# SaLFrostburn.net
KiCad netlist of a schematic drawn in EAGLE
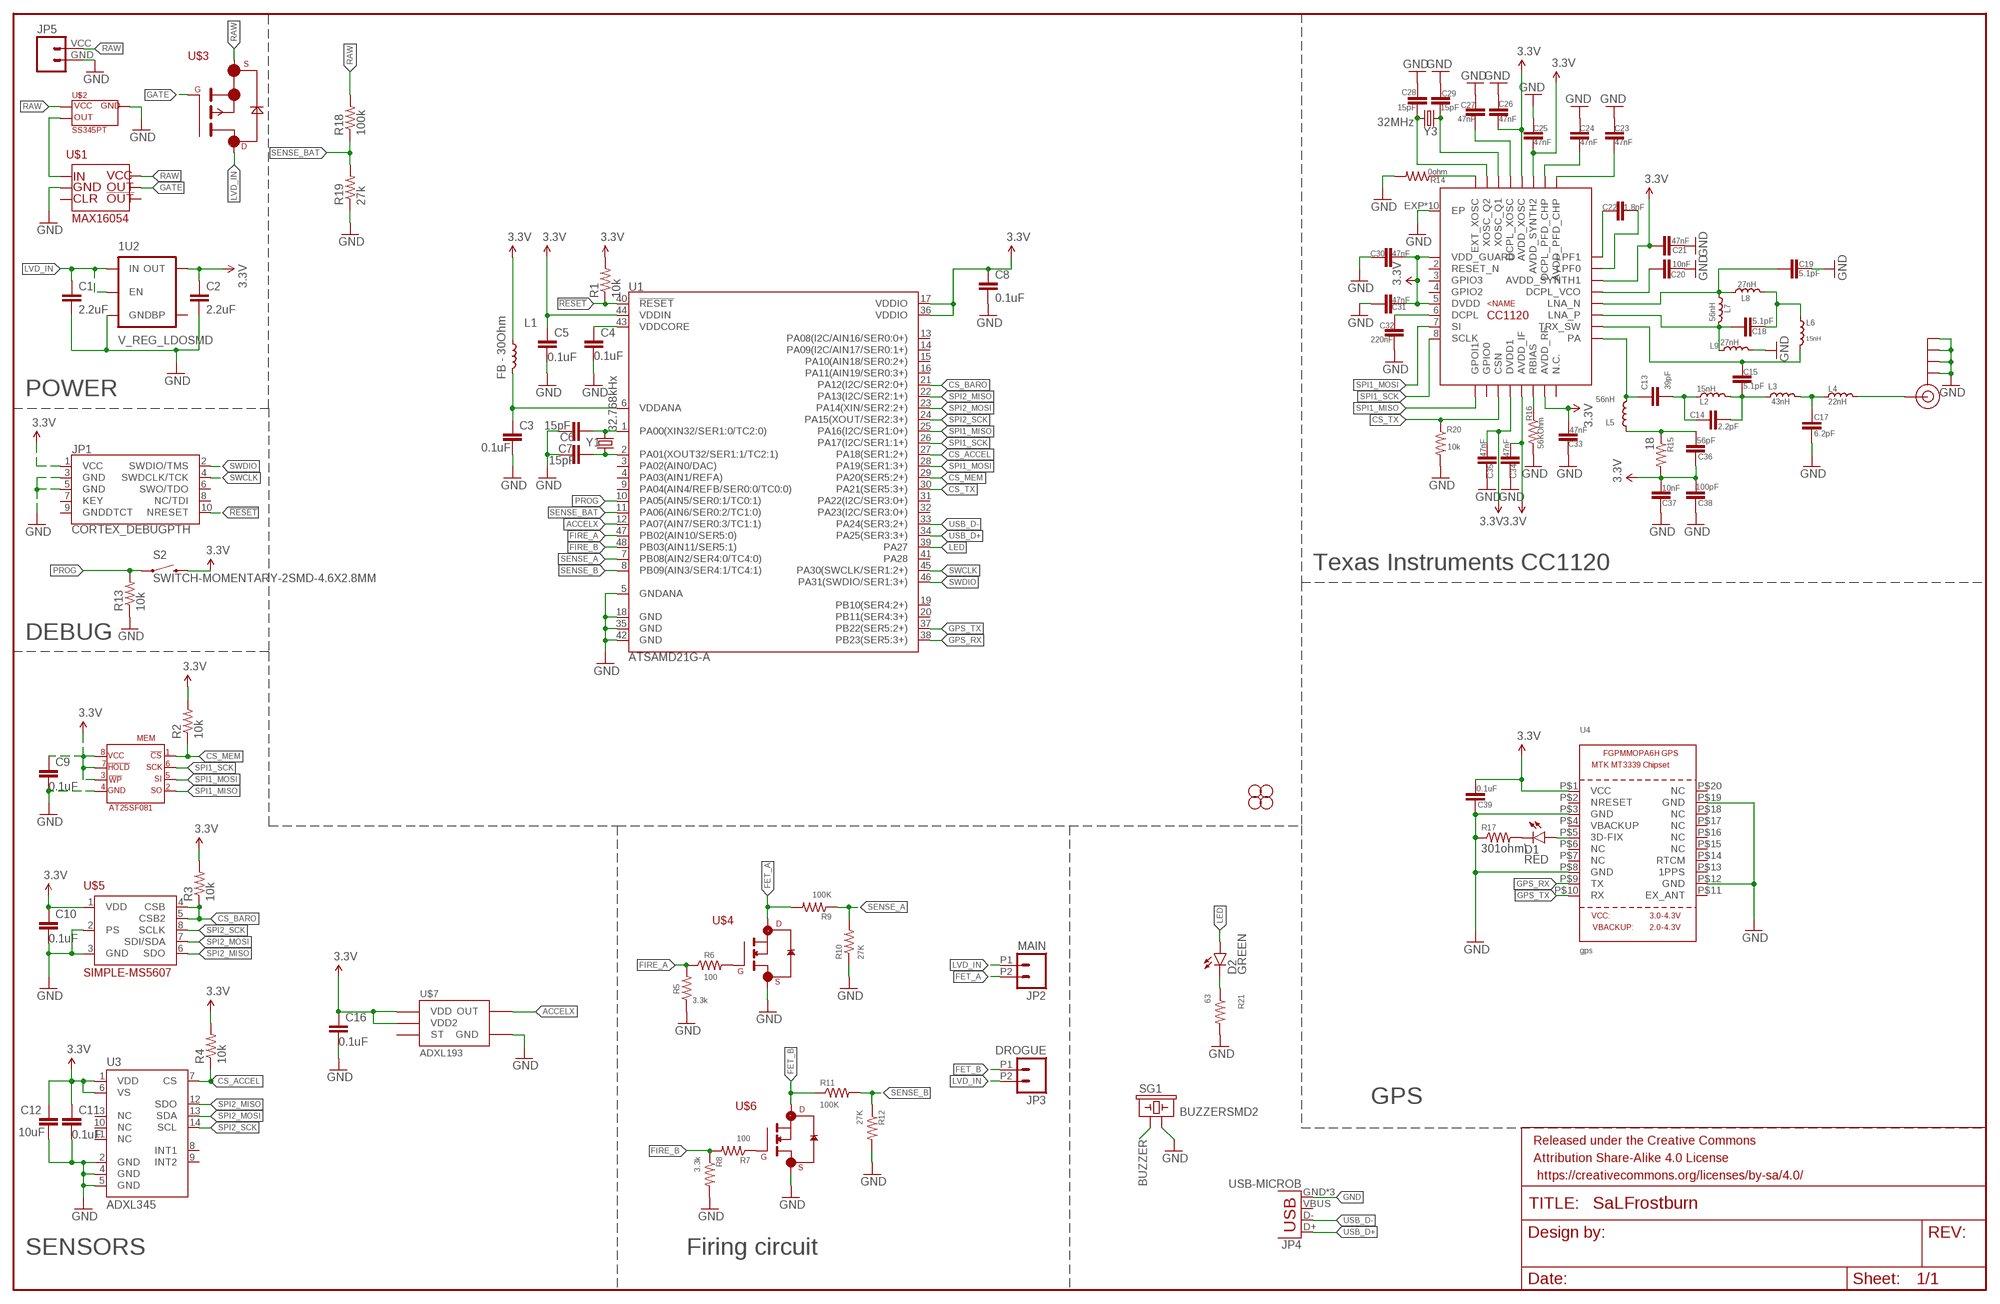
[diagram p0: schematic, sheet 1]

(export (version "E")
  (design (tool "Eeschema 10.0.6"))
  (components
    (comp (ref "1U2")
      (value "V_REG_LDOSMD")
      (footprint "eagle-import:SOT23-5")
      (libsource (lib "eagle-import") (part "V_REG_LDOSMD"))
    )
    (comp (ref "C1")
      (value "2.2uF")
      (footprint "eagle-import:0603-CAP")
      (libsource (lib "eagle-import") (part "CAP0603-CAP"))
    )
    (comp (ref "C2")
      (value "2.2uF")
      (footprint "eagle-import:0603-CAP")
      (libsource (lib "eagle-import") (part "CAP0603-CAP"))
    )
    (comp (ref "C3")
      (value "0.1uF")
      (footprint "eagle-import:0402-CAP")
      (libsource (lib "eagle-import") (part "SparkFun-Passives_CAP0402-CAP"))
    )
    (comp (ref "C4")
      (value "0.1uF")
      (footprint "eagle-import:0402-CAP")
      (libsource (lib "eagle-import") (part "SparkFun-Passives_CAP0402-CAP"))
    )
    (comp (ref "C5")
      (value "0.1uF")
      (footprint "eagle-import:0402-CAP")
      (libsource (lib "eagle-import") (part "SparkFun-Passives_CAP0402-CAP"))
    )
    (comp (ref "C6")
      (value "15pF")
      (footprint "eagle-import:0402-CAP")
      (libsource (lib "eagle-import") (part "SparkFun-Passives_CAP0402-CAP"))
    )
    (comp (ref "C7")
      (value "15pF")
      (footprint "eagle-import:0402-CAP")
      (libsource (lib "eagle-import") (part "SparkFun-Passives_CAP0402-CAP"))
    )
    (comp (ref "C8")
      (value "0.1uF")
      (footprint "eagle-import:0402-CAP")
      (libsource (lib "eagle-import") (part "SparkFun-Passives_CAP0402-CAP"))
    )
    (comp (ref "C9")
      (value "0.1uF")
      (footprint "eagle-import:0402-CAP")
      (libsource (lib "eagle-import") (part "SparkFun-Passives_CAP0402-CAP"))
    )
    (comp (ref "C10")
      (value "0.1uF")
      (footprint "eagle-import:0402-CAP")
      (libsource (lib "eagle-import") (part "SparkFun-Passives_CAP0402-CAP"))
    )
    (comp (ref "C11")
      (value "0.1uF")
      (footprint "eagle-import:0402-CAP")
      (libsource (lib "eagle-import") (part "SparkFun-Passives_CAP0402-CAP"))
    )
    (comp (ref "C12")
      (value "10uF")
      (footprint "eagle-import:0402-CAP")
      (libsource (lib "eagle-import") (part "SparkFun-Passives_CAP0402-CAP"))
    )
    (comp (ref "C13")
      (value "39pF")
      (footprint "eagle-import:0402-CAP")
      (libsource (lib "eagle-import") (part "CAP0402-CAP"))
    )
    (comp (ref "C14")
      (value "2.2pF")
      (footprint "eagle-import:0402-CAP")
      (libsource (lib "eagle-import") (part "CAP0402-CAP"))
    )
    (comp (ref "C15")
      (value "5.1pF")
      (footprint "eagle-import:0402-CAP")
      (libsource (lib "eagle-import") (part "CAP0402-CAP"))
    )
    (comp (ref "C16")
      (value "0.1uF")
      (footprint "eagle-import:0402-CAP")
      (libsource (lib "eagle-import") (part "SparkFun-Passives_CAP0402-CAP"))
    )
    (comp (ref "C17")
      (value "6.2pF")
      (footprint "eagle-import:0402-CAP")
      (libsource (lib "eagle-import") (part "CAP0402-CAP"))
    )
    (comp (ref "C18")
      (value "5.1pF")
      (footprint "eagle-import:0402-CAP")
      (libsource (lib "eagle-import") (part "CAP0402-CAP"))
    )
    (comp (ref "C19")
      (value "5.1pF")
      (footprint "eagle-import:0402-CAP")
      (libsource (lib "eagle-import") (part "CAP0402-CAP"))
    )
    (comp (ref "C20")
      (value "10nF")
      (footprint "eagle-import:0402-CAP")
      (libsource (lib "eagle-import") (part "CAP0402-CAP"))
    )
    (comp (ref "C21")
      (value "47nF")
      (footprint "eagle-import:0402-CAP")
      (libsource (lib "eagle-import") (part "CAP0402-CAP"))
    )
    (comp (ref "C22")
      (value "1.8nF")
      (footprint "eagle-import:0402-CAP")
      (libsource (lib "eagle-import") (part "CAP0402-CAP"))
    )
    (comp (ref "C23")
      (value "47nF")
      (footprint "eagle-import:0402-CAP")
      (libsource (lib "eagle-import") (part "CAP0402-CAP"))
    )
    (comp (ref "C24")
      (value "47nF")
      (footprint "eagle-import:0402-CAP")
      (libsource (lib "eagle-import") (part "CAP0402-CAP"))
    )
    (comp (ref "C25")
      (value "47nF")
      (footprint "eagle-import:0402-CAP")
      (libsource (lib "eagle-import") (part "CAP0402-CAP"))
    )
    (comp (ref "C26")
      (value "47nF")
      (footprint "eagle-import:0402-CAP")
      (libsource (lib "eagle-import") (part "CAP0402-CAP"))
    )
    (comp (ref "C27")
      (value "47nF")
      (footprint "eagle-import:0402-CAP")
      (libsource (lib "eagle-import") (part "CAP0402-CAP"))
    )
    (comp (ref "C28")
      (value "15pF")
      (footprint "eagle-import:0402-CAP")
      (libsource (lib "eagle-import") (part "CAP0402-CAP"))
    )
    (comp (ref "C29")
      (value "15pF")
      (footprint "eagle-import:0402-CAP")
      (libsource (lib "eagle-import") (part "CAP0402-CAP"))
    )
    (comp (ref "C30")
      (value "47nF")
      (footprint "eagle-import:0402-CAP")
      (libsource (lib "eagle-import") (part "CAP0402-CAP"))
    )
    (comp (ref "C31")
      (value "47nF")
      (footprint "eagle-import:0402-CAP")
      (libsource (lib "eagle-import") (part "CAP0402-CAP"))
    )
    (comp (ref "C32")
      (value "220nF")
      (footprint "eagle-import:0402-CAP")
      (libsource (lib "eagle-import") (part "CAP0402-CAP"))
    )
    (comp (ref "C33")
      (value "47nF")
      (footprint "eagle-import:0402-CAP")
      (libsource (lib "eagle-import") (part "CAP0402-CAP"))
    )
    (comp (ref "C34")
      (value "47nF")
      (footprint "eagle-import:0402-CAP")
      (libsource (lib "eagle-import") (part "CAP0402-CAP"))
    )
    (comp (ref "C35")
      (value "47nF")
      (footprint "eagle-import:0402-CAP")
      (libsource (lib "eagle-import") (part "CAP0402-CAP"))
    )
    (comp (ref "C36")
      (value "56pF")
      (footprint "eagle-import:0402-CAP")
      (libsource (lib "eagle-import") (part "CAP0402-CAP"))
    )
    (comp (ref "C37")
      (value "10nF")
      (footprint "eagle-import:0402-CAP")
      (libsource (lib "eagle-import") (part "CAP0402-CAP"))
    )
    (comp (ref "C38")
      (value "100pF")
      (footprint "eagle-import:0402-CAP")
      (libsource (lib "eagle-import") (part "CAP0402-CAP"))
    )
    (comp (ref "C39")
      (value "0.1uF")
      (footprint "eagle-import:0402-CAP")
      (libsource (lib "eagle-import") (part "CAP0402-CAP"))
    )
    (comp (ref "D1")
      (value "RED")
      (footprint "eagle-import:LED-0603")
      (libsource (lib "eagle-import") (part "LED-RED0603"))
    )
    (comp (ref "D2")
      (value "GREEN")
      (footprint "eagle-import:LED-1206")
      (libsource (lib "eagle-import") (part "LED-GREEN1206"))
    )
    (comp (ref "FRAME1")
      (value "FRAME-LEDGER")
      (footprint "eagle-import:CREATIVE_COMMONS")
      (libsource (lib "eagle-import") (part "FRAME-LEDGER"))
    )
    (comp (ref "J$1")
      (value "SMA_EDGE")
      (footprint "eagle-import:SMA-EDGE")
      (libsource (lib "eagle-import") (part "SMA_EDGE"))
    )
    (comp (ref "JP1")
      (value "CORTEX_DEBUGPTH")
      (footprint "eagle-import:2X5-PTH-1.27MM")
      (libsource (lib "eagle-import") (part "CORTEX_DEBUGPTH"))
    )
    (comp (ref "JP2")
      (value "MAIN")
      (footprint "eagle-import:1X02_2.54_SCREWTERM")
      (libsource (lib "eagle-import") (part "M022.54MM_SCREWTERM"))
    )
    (comp (ref "JP3")
      (value "DROGUE")
      (footprint "eagle-import:1X02_2.54_SCREWTERM")
      (libsource (lib "eagle-import") (part "M022.54MM_SCREWTERM"))
    )
    (comp (ref "JP4")
      (value "USB-MICROB")
      (footprint "eagle-import:USB-MICROB")
      (libsource (lib "eagle-import") (part "USB-MICROB"))
    )
    (comp (ref "JP5")
      (value "M024UCON-15767")
      (footprint "eagle-import:JST-2-SMD-VERT")
      (libsource (lib "eagle-import") (part "M024UCON-15767"))
    )
    (comp (ref "L1")
      (value "FB - 30Ohm")
      (footprint "eagle-import:0603")
      (libsource (lib "eagle-import") (part "INDUCTOR0603"))
    )
    (comp (ref "L2")
      (value "15nH")
      (footprint "eagle-import:C0402")
      (libsource (lib "eagle-import") (part "INDUCTOR0402"))
    )
    (comp (ref "L3")
      (value "43nH")
      (footprint "eagle-import:C0402")
      (libsource (lib "eagle-import") (part "INDUCTOR0402"))
    )
    (comp (ref "L4")
      (value "22nH")
      (footprint "eagle-import:C0402")
      (libsource (lib "eagle-import") (part "INDUCTOR0402"))
    )
    (comp (ref "L5")
      (value "56nH")
      (footprint "eagle-import:C0402")
      (libsource (lib "eagle-import") (part "INDUCTOR0402"))
    )
    (comp (ref "L6")
      (value "15nH")
      (footprint "eagle-import:C0402")
      (libsource (lib "eagle-import") (part "INDUCTOR0402"))
    )
    (comp (ref "L7")
      (value "56nH")
      (footprint "eagle-import:C0402")
      (libsource (lib "eagle-import") (part "INDUCTOR0402"))
    )
    (comp (ref "L8")
      (value "27nH")
      (footprint "eagle-import:C0402")
      (libsource (lib "eagle-import") (part "INDUCTOR0402"))
    )
    (comp (ref "L9")
      (value "27nH")
      (footprint "eagle-import:C0402")
      (libsource (lib "eagle-import") (part "INDUCTOR0402"))
    )
    (comp (ref "MEM")
      (value "AT25SF081")
      (footprint "eagle-import:AT25SF081")
      (libsource (lib "eagle-import") (part "AT25SF081"))
    )
    (comp (ref "R1")
      (value "10k")
      (footprint "eagle-import:0402-RES")
      (libsource (lib "eagle-import") (part "RESISTOR0402-RES"))
    )
    (comp (ref "R2")
      (value "10k")
      (footprint "eagle-import:0402-RES")
      (libsource (lib "eagle-import") (part "RESISTOR0402-RES"))
    )
    (comp (ref "R3")
      (value "10k")
      (footprint "eagle-import:0402-RES")
      (libsource (lib "eagle-import") (part "RESISTOR0402-RES"))
    )
    (comp (ref "R4")
      (value "10k")
      (footprint "eagle-import:0402-RES")
      (libsource (lib "eagle-import") (part "RESISTOR0402-RES"))
    )
    (comp (ref "R5")
      (value "3.3k")
      (footprint "eagle-import:0402-RES")
      (libsource (lib "eagle-import") (part "RESISTOR0402"))
    )
    (comp (ref "R6")
      (value "100")
      (footprint "eagle-import:0402-RES")
      (libsource (lib "eagle-import") (part "RESISTOR0402"))
    )
    (comp (ref "R7")
      (value "100")
      (footprint "eagle-import:0402-RES")
      (libsource (lib "eagle-import") (part "RESISTOR0402"))
    )
    (comp (ref "R8")
      (value "3.3k")
      (footprint "eagle-import:0402-RES")
      (libsource (lib "eagle-import") (part "RESISTOR0402"))
    )
    (comp (ref "R9")
      (value "100K")
      (footprint "eagle-import:0402-RES")
      (libsource (lib "eagle-import") (part "RESISTOR0402"))
    )
    (comp (ref "R10")
      (value "27K")
      (footprint "eagle-import:0402-RES")
      (libsource (lib "eagle-import") (part "RESISTOR0402"))
    )
    (comp (ref "R11")
      (value "100K")
      (footprint "eagle-import:0402-RES")
      (libsource (lib "eagle-import") (part "RESISTOR0402"))
    )
    (comp (ref "R12")
      (value "27K")
      (footprint "eagle-import:0402-RES")
      (libsource (lib "eagle-import") (part "RESISTOR0402"))
    )
    (comp (ref "R13")
      (value "10k")
      (footprint "eagle-import:0402-RES")
      (libsource (lib "eagle-import") (part "RESISTOR0402-RES"))
    )
    (comp (ref "R14")
      (value "0ohm")
      (footprint "eagle-import:0402-RES")
      (libsource (lib "eagle-import") (part "RESISTOR0402-RES"))
    )
    (comp (ref "R15")
      (value "18")
      (footprint "eagle-import:0402-RES")
      (libsource (lib "eagle-import") (part "RESISTOR0402-RES"))
    )
    (comp (ref "R16")
      (value "56KOhm")
      (footprint "eagle-import:0402-RES")
      (libsource (lib "eagle-import") (part "RESISTOR0402-RES"))
    )
    (comp (ref "R17")
      (value "301ohm\\")
      (footprint "eagle-import:0402-RES")
      (libsource (lib "eagle-import") (part "RESISTOR0402-RES"))
    )
    (comp (ref "R18")
      (value "100k")
      (footprint "eagle-import:0402-RES")
      (libsource (lib "eagle-import") (part "RESISTOR0402-RES"))
    )
    (comp (ref "R19")
      (value "27k")
      (footprint "eagle-import:0402-RES")
      (libsource (lib "eagle-import") (part "RESISTOR0402-RES"))
    )
    (comp (ref "R20")
      (value "10k")
      (footprint "eagle-import:0402-RES")
      (libsource (lib "eagle-import") (part "RESISTOR0402-RES"))
    )
    (comp (ref "R21")
      (value "63")
      (footprint "eagle-import:0402-RES")
      (libsource (lib "eagle-import") (part "RESISTOR0402"))
    )
    (comp (ref "S2")
      (value "SWITCH-MOMENTARY-2SMD-4.6X2.8MM")
      (footprint "eagle-import:TACTILE_SWITCH_SMD_4.6X2.8MM")
      (libsource (lib "eagle-import") (part "SWITCH-MOMENTARY-2SMD-4.6X2.8MM"))
    )
    (comp (ref "SG1")
      (value "BUZZERSMD2")
      (footprint "eagle-import:BUZZER-CCV")
      (libsource (lib "eagle-import") (part "BUZZERSMD2"))
    )
    (comp (ref "STANDOFF1")
      (value "STAND-OFF")
      (footprint "eagle-import:STAND-OFF")
      (libsource (lib "eagle-import") (part "STAND-OFF"))
    )
    (comp (ref "STANDOFF2")
      (value "STAND-OFF")
      (footprint "eagle-import:STAND-OFF")
      (libsource (lib "eagle-import") (part "STAND-OFF"))
    )
    (comp (ref "STANDOFF3")
      (value "STAND-OFF")
      (footprint "eagle-import:STAND-OFF")
      (libsource (lib "eagle-import") (part "STAND-OFF"))
    )
    (comp (ref "STANDOFF4")
      (value "STAND-OFF")
      (footprint "eagle-import:STAND-OFF")
      (libsource (lib "eagle-import") (part "STAND-OFF"))
    )
    (comp (ref "TX/RX")
      (value "CC1120")
      (footprint "eagle-import:CC1120")
      (libsource (lib "eagle-import") (part "CC1120"))
    )
    (comp (ref "U$1")
      (value "MAX16054")
      (footprint "eagle-import:MAX16054")
      (libsource (lib "eagle-import") (part "MAX16054"))
    )
    (comp (ref "U$2")
      (value "SS345PT")
      (footprint "eagle-import:SS345PT")
      (libsource (lib "eagle-import") (part "SS345PT"))
    )
    (comp (ref "U$3")
      (value "SI7615ADN")
      (footprint "eagle-import:SI7615ADN")
      (libsource (lib "eagle-import") (part "SI7615ADN"))
    )
    (comp (ref "U$4")
      (value "SIS410DN")
      (footprint "eagle-import:POWERPACK1212-8")
      (libsource (lib "eagle-import") (part "SIS410DN"))
    )
    (comp (ref "U$5")
      (value "SIMPLE-MS5607")
      (footprint "eagle-import:MS5607")
      (libsource (lib "eagle-import") (part "SIMPLE-MS5607"))
    )
    (comp (ref "U$6")
      (value "SIS410DN")
      (footprint "eagle-import:POWERPACK1212-8")
      (libsource (lib "eagle-import") (part "SIS410DN"))
    )
    (comp (ref "U$7")
      (value "ADXL193")
      (footprint "eagle-import:ADXL193")
      (libsource (lib "eagle-import") (part "ADXL193"))
    )
    (comp (ref "U1")
      (value "ATSAMD21G-A")
      (footprint "eagle-import:TQFP-48")
      (libsource (lib "eagle-import") (part "ATSAMD21G-A"))
    )
    (comp (ref "U3")
      (value "ADXL345")
      (footprint "eagle-import:LGA14")
      (libsource (lib "eagle-import") (part "ADXL345"))
    )
    (comp (ref "U4")
      (value "gps")
      (footprint "eagle-import:FGPMMOPA6H")
      (libsource (lib "eagle-import") (part "GPS_FGPMMOPA6H"))
    )
    (comp (ref "Y1")
      (value "32.768kHx")
      (footprint "eagle-import:CRYSTAL-SMD-3.2X1.5MM")
      (libsource (lib "eagle-import") (part "CRYSTAL3.2X1.5MM"))
    )
    (comp (ref "Y3")
      (value "32MHz")
      (footprint "eagle-import:CRYSTAL-SMD-5X3")
      (libsource (lib "eagle-import") (part "CRYSTAL5X3"))
    )
  )
  (nets
    (net (code "1") (name "/BUZZER") (class "Default")
      (node (ref "SG1") (pin "+") (pinfunction "1_+") (pintype "passive"))
    )
    (net (code "2") (name "/~{RESET}") (class "Default")
      (node (ref "JP1") (pin "10") (pinfunction "NRESET_10") (pintype "bidirectional"))
      (node (ref "R1") (pin "1") (pinfunction "1_1") (pintype "passive"))
      (node (ref "U1") (pin "40") (pinfunction "~{RESET}_40") (pintype "bidirectional"))
    )
    (net (code "3") (name "3.3V") (class "Default")
      (node (ref "1U2") (pin "5") (pinfunction "OUT_5") (pintype "passive"))
      (node (ref "C10") (pin "1") (pinfunction "1_1") (pintype "passive"))
      (node (ref "C11") (pin "1") (pinfunction "1_1") (pintype "passive"))
      (node (ref "C12") (pin "1") (pinfunction "1_1") (pintype "passive"))
      (node (ref "C16") (pin "1") (pinfunction "1_1") (pintype "passive"))
      (node (ref "C2") (pin "1") (pinfunction "1_1") (pintype "passive"))
      (node (ref "C21") (pin "1") (pinfunction "1_1") (pintype "passive"))
      (node (ref "C25") (pin "2") (pinfunction "2_2") (pintype "passive"))
      (node (ref "C26") (pin "2") (pinfunction "2_2") (pintype "passive"))
      (node (ref "C30") (pin "2") (pinfunction "2_2") (pintype "passive"))
      (node (ref "C31") (pin "2") (pinfunction "2_2") (pintype "passive"))
      (node (ref "C33") (pin "2") (pinfunction "2_2") (pintype "passive"))
      (node (ref "C34") (pin "2") (pinfunction "2_2") (pintype "passive"))
      (node (ref "C35") (pin "2") (pinfunction "2_2") (pintype "passive"))
      (node (ref "C36") (pin "1") (pinfunction "1_1") (pintype "passive"))
      (node (ref "C37") (pin "2") (pinfunction "2_2") (pintype "passive"))
      (node (ref "C38") (pin "2") (pinfunction "2_2") (pintype "passive"))
      (node (ref "C39") (pin "2") (pinfunction "2_2") (pintype "passive"))
      (node (ref "C5") (pin "1") (pinfunction "1_1") (pintype "passive"))
      (node (ref "C8") (pin "1") (pinfunction "1_1") (pintype "passive"))
      (node (ref "C9") (pin "1") (pinfunction "1_1") (pintype "passive"))
      (node (ref "JP1") (pin "1") (pinfunction "VCC_1") (pintype "bidirectional"))
      (node (ref "L1") (pin "1") (pinfunction "1_1") (pintype "passive"))
      (node (ref "MEM") (pin "!HOLD") (pinfunction "~{HOLD}_!HOLD") (pintype "bidirectional"))
      (node (ref "MEM") (pin "!WP") (pinfunction "~{WP}_!WP") (pintype "bidirectional"))
      (node (ref "MEM") (pin "VCC") (pinfunction "VCC_VCC") (pintype "bidirectional"))
      (node (ref "R1") (pin "2") (pinfunction "2_2") (pintype "passive"))
      (node (ref "R15") (pin "2") (pinfunction "2_2") (pintype "passive"))
      (node (ref "R2") (pin "2") (pinfunction "2_2") (pintype "passive"))
      (node (ref "R3") (pin "2") (pinfunction "2_2") (pintype "passive"))
      (node (ref "R4") (pin "2") (pinfunction "2_2") (pintype "passive"))
      (node (ref "S2") (pin "3") (pinfunction "2_3") (pintype "passive"))
      (node (ref "S2") (pin "4") (pinfunction "2_4") (pintype "passive"))
      (node (ref "TX/RX") (pin "1") (pinfunction "VDD_GUARD_1") (pintype "bidirectional"))
      (node (ref "TX/RX") (pin "12") (pinfunction "DVDD1_12") (pintype "bidirectional"))
      (node (ref "TX/RX") (pin "13") (pinfunction "AVDD_IF_13") (pintype "bidirectional"))
      (node (ref "TX/RX") (pin "15") (pinfunction "AVDD_RF_15") (pintype "bidirectional"))
      (node (ref "TX/RX") (pin "22") (pinfunction "AVDD_SYNTH1_22") (pintype "bidirectional"))
      (node (ref "TX/RX") (pin "27") (pinfunction "AVDD_SYNTH2_27") (pintype "bidirectional"))
      (node (ref "TX/RX") (pin "28") (pinfunction "AVDD_XOSC_28") (pintype "bidirectional"))
      (node (ref "TX/RX") (pin "5") (pinfunction "DVDD_5") (pintype "bidirectional"))
      (node (ref "U$5") (pin "1") (pinfunction "VDD_1") (pintype "bidirectional"))
      (node (ref "U$7") (pin "P$7") (pinfunction "VDD_P$7") (pintype "bidirectional"))
      (node (ref "U$7") (pin "P$8") (pinfunction "VDD2_P$8") (pintype "bidirectional"))
      (node (ref "U1") (pin "17") (pinfunction "VDDIO_17") (pintype "bidirectional"))
      (node (ref "U1") (pin "36") (pinfunction "VDDIO_36") (pintype "bidirectional"))
      (node (ref "U1") (pin "44") (pinfunction "VDDIN_44") (pintype "bidirectional"))
      (node (ref "U3") (pin "1") (pinfunction "VDD_1") (pintype "bidirectional"))
      (node (ref "U3") (pin "6") (pinfunction "VS_6") (pintype "bidirectional"))
      (node (ref "U4") (pin "P$1") (pinfunction "VCC_P$1") (pintype "bidirectional"))
    )
    (net (code "4") (name "ACCELX") (class "Default")
      (node (ref "U$7") (pin "P$6") (pinfunction "OUT_P$6") (pintype "bidirectional"))
      (node (ref "U1") (pin "12") (pinfunction "PA07(AIN7/SER0:3/TC1:1)_12") (pintype "bidirectional"))
    )
    (net (code "5") (name "CS_ACCEL") (class "Default")
      (node (ref "R4") (pin "1") (pinfunction "1_1") (pintype "passive"))
      (node (ref "U1") (pin "27") (pinfunction "PA18(SER1:2+)_27") (pintype "bidirectional"))
      (node (ref "U3") (pin "7") (pinfunction "CS_7") (pintype "bidirectional"))
    )
    (net (code "6") (name "CS_BARO") (class "Default")
      (node (ref "R3") (pin "1") (pinfunction "1_1") (pintype "passive"))
      (node (ref "U$5") (pin "4") (pinfunction "CSB_4") (pintype "bidirectional"))
      (node (ref "U$5") (pin "5") (pinfunction "CSB2_5") (pintype "bidirectional"))
      (node (ref "U1") (pin "21") (pinfunction "PA12(I2C/SER2:0+)_21") (pintype "bidirectional"))
    )
    (net (code "7") (name "CS_MEM") (class "Default")
      (node (ref "MEM") (pin "!CS") (pinfunction "~{CS}_!CS") (pintype "bidirectional"))
      (node (ref "R2") (pin "1") (pinfunction "1_1") (pintype "passive"))
      (node (ref "U1") (pin "29") (pinfunction "PA20(SER5:2+)_29") (pintype "bidirectional"))
    )
    (net (code "8") (name "CS_TX") (class "Default")
      (node (ref "R20") (pin "1") (pinfunction "1_1") (pintype "passive"))
      (node (ref "TX/RX") (pin "11") (pinfunction "CSN_11") (pintype "bidirectional"))
      (node (ref "U1") (pin "30") (pinfunction "PA21(SER5:3+)_30") (pintype "bidirectional"))
    )
    (net (code "9") (name "FET_A") (class "Default")
      (node (ref "JP2") (pin "P2") (pinfunction "2_P2") (pintype "passive"))
      (node (ref "R9") (pin "2") (pinfunction "2_2") (pintype "passive"))
      (node (ref "U$4") (pin "5") (pinfunction "D_5") (pintype "bidirectional"))
      (node (ref "U$4") (pin "6") (pinfunction "D_6") (pintype "bidirectional"))
      (node (ref "U$4") (pin "7") (pinfunction "D_7") (pintype "bidirectional"))
      (node (ref "U$4") (pin "8") (pinfunction "D_8") (pintype "bidirectional"))
    )
    (net (code "10") (name "FET_B") (class "Default")
      (node (ref "JP3") (pin "P1") (pinfunction "1_P1") (pintype "passive"))
      (node (ref "R11") (pin "1") (pinfunction "1_1") (pintype "passive"))
      (node (ref "U$6") (pin "5") (pinfunction "D_5") (pintype "bidirectional"))
      (node (ref "U$6") (pin "6") (pinfunction "D_6") (pintype "bidirectional"))
      (node (ref "U$6") (pin "7") (pinfunction "D_7") (pintype "bidirectional"))
      (node (ref "U$6") (pin "8") (pinfunction "D_8") (pintype "bidirectional"))
    )
    (net (code "11") (name "FIRE_A") (class "Default")
      (node (ref "R5") (pin "2") (pinfunction "2_2") (pintype "passive"))
      (node (ref "R6") (pin "1") (pinfunction "1_1") (pintype "passive"))
      (node (ref "U1") (pin "47") (pinfunction "PB02(AIN10/SER5:0)_47") (pintype "bidirectional"))
    )
    (net (code "12") (name "FIRE_B") (class "Default")
      (node (ref "R7") (pin "2") (pinfunction "2_2") (pintype "passive"))
      (node (ref "R8") (pin "1") (pinfunction "1_1") (pintype "passive"))
      (node (ref "U1") (pin "48") (pinfunction "PB03(AIN11/SER5:1)_48") (pintype "bidirectional"))
    )
    (net (code "13") (name "GATE") (class "Default")
      (node (ref "U$1") (pin "OUT") (pinfunction "OUT_OUT") (pintype "bidirectional"))
      (node (ref "U$3") (pin "G") (pinfunction "G_G") (pintype "bidirectional"))
    )
    (net (code "14") (name "GND") (class "Default")
      (node (ref "1U2") (pin "2") (pinfunction "GND_2") (pintype "input"))
      (node (ref "C1") (pin "2") (pinfunction "2_2") (pintype "passive"))
      (node (ref "C10") (pin "2") (pinfunction "2_2") (pintype "passive"))
      (node (ref "C11") (pin "2") (pinfunction "2_2") (pintype "passive"))
      (node (ref "C12") (pin "2") (pinfunction "2_2") (pintype "passive"))
      (node (ref "C16") (pin "2") (pinfunction "2_2") (pintype "passive"))
      (node (ref "C17") (pin "2") (pinfunction "2_2") (pintype "passive"))
      (node (ref "C19") (pin "2") (pinfunction "2_2") (pintype "passive"))
      (node (ref "C2") (pin "2") (pinfunction "2_2") (pintype "passive"))
      (node (ref "C20") (pin "2") (pinfunction "2_2") (pintype "passive"))
      (node (ref "C21") (pin "2") (pinfunction "2_2") (pintype "passive"))
      (node (ref "C23") (pin "1") (pinfunction "1_1") (pintype "passive"))
      (node (ref "C24") (pin "1") (pinfunction "1_1") (pintype "passive"))
      (node (ref "C25") (pin "1") (pinfunction "1_1") (pintype "passive"))
      (node (ref "C26") (pin "1") (pinfunction "1_1") (pintype "passive"))
      (node (ref "C27") (pin "1") (pinfunction "1_1") (pintype "passive"))
      (node (ref "C28") (pin "1") (pinfunction "1_1") (pintype "passive"))
      (node (ref "C29") (pin "1") (pinfunction "1_1") (pintype "passive"))
      (node (ref "C3") (pin "2") (pinfunction "2_2") (pintype "passive"))
      (node (ref "C30") (pin "1") (pinfunction "1_1") (pintype "passive"))
      (node (ref "C31") (pin "1") (pinfunction "1_1") (pintype "passive"))
      (node (ref "C32") (pin "1") (pinfunction "1_1") (pintype "passive"))
      (node (ref "C33") (pin "1") (pinfunction "1_1") (pintype "passive"))
      (node (ref "C34") (pin "1") (pinfunction "1_1") (pintype "passive"))
      (node (ref "C35") (pin "1") (pinfunction "1_1") (pintype "passive"))
      (node (ref "C37") (pin "1") (pinfunction "1_1") (pintype "passive"))
      (node (ref "C38") (pin "1") (pinfunction "1_1") (pintype "passive"))
      (node (ref "C39") (pin "1") (pinfunction "1_1") (pintype "passive"))
      (node (ref "C4") (pin "2") (pinfunction "2_2") (pintype "passive"))
      (node (ref "C5") (pin "2") (pinfunction "2_2") (pintype "passive"))
      (node (ref "C6") (pin "2") (pinfunction "2_2") (pintype "passive"))
      (node (ref "C7") (pin "2") (pinfunction "2_2") (pintype "passive"))
      (node (ref "C8") (pin "2") (pinfunction "2_2") (pintype "passive"))
      (node (ref "C9") (pin "2") (pinfunction "2_2") (pintype "passive"))
      (node (ref "J$1") (pin "GND@0") (pinfunction "GND_GND@0") (pintype "bidirectional"))
      (node (ref "J$1") (pin "GND@1") (pinfunction "GND_GND@1") (pintype "bidirectional"))
      (node (ref "J$1") (pin "GND@2") (pinfunction "GND_GND@2") (pintype "bidirectional"))
      (node (ref "J$1") (pin "GND@3") (pinfunction "GND_GND@3") (pintype "bidirectional"))
      (node (ref "JP1") (pin "3") (pinfunction "GND_3") (pintype "bidirectional"))
      (node (ref "JP1") (pin "5") (pinfunction "GND_5") (pintype "bidirectional"))
      (node (ref "JP4") (pin "GND") (pinfunction "GND_GND") (pintype "bidirectional"))
      (node (ref "JP4") (pin "MT1") (pinfunction "GND_MT1") (pintype "bidirectional"))
      (node (ref "JP4") (pin "MT2") (pinfunction "GND_MT2") (pintype "bidirectional"))
      (node (ref "JP5") (pin "GND") (pinfunction "1_GND") (pintype "passive"))
      (node (ref "L9") (pin "2") (pinfunction "2_2") (pintype "passive"))
      (node (ref "MEM") (pin "GND") (pinfunction "GND_GND") (pintype "bidirectional"))
      (node (ref "R10") (pin "1") (pinfunction "1_1") (pintype "passive"))
      (node (ref "R12") (pin "2") (pinfunction "2_2") (pintype "passive"))
      (node (ref "R13") (pin "1") (pinfunction "1_1") (pintype "passive"))
      (node (ref "R14") (pin "2") (pinfunction "2_2") (pintype "passive"))
      (node (ref "R16") (pin "2") (pinfunction "2_2") (pintype "passive"))
      (node (ref "R17") (pin "1") (pinfunction "1_1") (pintype "passive"))
      (node (ref "R19") (pin "1") (pinfunction "1_1") (pintype "passive"))
      (node (ref "R20") (pin "2") (pinfunction "2_2") (pintype "passive"))
      (node (ref "R21") (pin "2") (pinfunction "2_2") (pintype "passive"))
      (node (ref "R5") (pin "1") (pinfunction "1_1") (pintype "passive"))
      (node (ref "R8") (pin "2") (pinfunction "2_2") (pintype "passive"))
      (node (ref "SG1") (pin "-") (pinfunction "2_-") (pintype "passive"))
      (node (ref "TX/RX") (pin "EXP") (pinfunction "EP_EXP") (pintype "bidirectional"))
      (node (ref "TX/RX") (pin "EXP@1") (pinfunction "EP_EXP@1") (pintype "bidirectional"))
      (node (ref "TX/RX") (pin "EXP@2") (pinfunction "EP_EXP@2") (pintype "bidirectional"))
      (node (ref "TX/RX") (pin "EXP@3") (pinfunction "EP_EXP@3") (pintype "bidirectional"))
      (node (ref "TX/RX") (pin "EXP@4") (pinfunction "EP_EXP@4") (pintype "bidirectional"))
      (node (ref "TX/RX") (pin "EXP@5") (pinfunction "EP_EXP@5") (pintype "bidirectional"))
      (node (ref "TX/RX") (pin "EXP@6") (pinfunction "EP_EXP@6") (pintype "bidirectional"))
      (node (ref "TX/RX") (pin "EXP@7") (pinfunction "EP_EXP@7") (pintype "bidirectional"))
      (node (ref "TX/RX") (pin "EXP@8") (pinfunction "EP_EXP@8") (pintype "bidirectional"))
      (node (ref "TX/RX") (pin "EXP@9") (pinfunction "EP_EXP@9") (pintype "bidirectional"))
      (node (ref "U$1") (pin "GND") (pinfunction "GND_GND") (pintype "bidirectional"))
      (node (ref "U$2") (pin "GND") (pinfunction "GND_GND") (pintype "bidirectional"))
      (node (ref "U$4") (pin "1") (pinfunction "S_1") (pintype "bidirectional"))
      (node (ref "U$4") (pin "2") (pinfunction "S_2") (pintype "bidirectional"))
      (node (ref "U$4") (pin "3") (pinfunction "S_3") (pintype "bidirectional"))
      (node (ref "U$5") (pin "2") (pinfunction "PS_2") (pintype "bidirectional"))
      (node (ref "U$5") (pin "3") (pinfunction "GND_3") (pintype "bidirectional"))
      (node (ref "U$6") (pin "1") (pinfunction "S_1") (pintype "bidirectional"))
      (node (ref "U$6") (pin "2") (pinfunction "S_2") (pintype "bidirectional"))
      (node (ref "U$6") (pin "3") (pinfunction "S_3") (pintype "bidirectional"))
      (node (ref "U$7") (pin "P$3") (pinfunction "GND_P$3") (pintype "bidirectional"))
      (node (ref "U1") (pin "18") (pinfunction "GND_18") (pintype "bidirectional"))
      (node (ref "U1") (pin "35") (pinfunction "GND_35") (pintype "bidirectional"))
      (node (ref "U1") (pin "42") (pinfunction "GND_42") (pintype "bidirectional"))
      (node (ref "U1") (pin "5") (pinfunction "GNDANA_5") (pintype "bidirectional"))
      (node (ref "U3") (pin "2") (pinfunction "GND_2") (pintype "bidirectional"))
      (node (ref "U3") (pin "4") (pinfunction "GND_4") (pintype "bidirectional"))
      (node (ref "U3") (pin "5") (pinfunction "GND_5") (pintype "bidirectional"))
      (node (ref "U4") (pin "P$12") (pinfunction "GND_P$12") (pintype "bidirectional"))
      (node (ref "U4") (pin "P$19") (pinfunction "GND_P$19") (pintype "bidirectional"))
      (node (ref "U4") (pin "P$3") (pinfunction "GND_P$3") (pintype "bidirectional"))
      (node (ref "U4") (pin "P$8") (pinfunction "GND_P$8") (pintype "bidirectional"))
    )
    (net (code "15") (name "GPS_RX") (class "Default")
      (node (ref "U1") (pin "38") (pinfunction "PB23(SER5:3+)_38") (pintype "bidirectional"))
      (node (ref "U4") (pin "P$9") (pinfunction "TX_P$9") (pintype "bidirectional"))
    )
    (net (code "16") (name "GPS_TX") (class "Default")
      (node (ref "U1") (pin "37") (pinfunction "PB22(SER5:2+)_37") (pintype "bidirectional"))
      (node (ref "U4") (pin "P$10") (pinfunction "RX_P$10") (pintype "bidirectional"))
    )
    (net (code "17") (name "LED") (class "Default")
      (node (ref "D2") (pin "A") (pinfunction "A_A") (pintype "passive"))
      (node (ref "U1") (pin "39") (pinfunction "PA27_39") (pintype "bidirectional"))
    )
    (net (code "18") (name "LVD_IN") (class "Default")
      (node (ref "1U2") (pin "1") (pinfunction "IN_1") (pintype "input"))
      (node (ref "1U2") (pin "3") (pinfunction "EN_3") (pintype "input"))
      (node (ref "C1") (pin "1") (pinfunction "1_1") (pintype "passive"))
      (node (ref "JP2") (pin "P1") (pinfunction "1_P1") (pintype "passive"))
      (node (ref "JP3") (pin "P2") (pinfunction "2_P2") (pintype "passive"))
      (node (ref "U$3") (pin "D1") (pinfunction "D_D1") (pintype "bidirectional"))
      (node (ref "U$3") (pin "D2") (pinfunction "D_D2") (pintype "bidirectional"))
      (node (ref "U$3") (pin "D3") (pinfunction "D_D3") (pintype "bidirectional"))
      (node (ref "U$3") (pin "D4") (pinfunction "D_D4") (pintype "bidirectional"))
    )
    (net (code "19") (name "Net-(C13-Pad2)") (class "Default")
      (node (ref "C13") (pin "2") (pinfunction "2_2") (pintype "passive"))
      (node (ref "C14") (pin "1") (pinfunction "1_1") (pintype "passive"))
      (node (ref "L2") (pin "1") (pinfunction "1_1") (pintype "passive"))
    )
    (net (code "20") (name "Net-(C14-Pad2)") (class "Default")
      (node (ref "C14") (pin "2") (pinfunction "2_2") (pintype "passive"))
      (node (ref "C15") (pin "1") (pinfunction "1_1") (pintype "passive"))
      (node (ref "L2") (pin "2") (pinfunction "2_2") (pintype "passive"))
      (node (ref "L3") (pin "1") (pinfunction "1_1") (pintype "passive"))
    )
    (net (code "21") (name "Net-(C17-Pad1)") (class "Default")
      (node (ref "C17") (pin "1") (pinfunction "1_1") (pintype "passive"))
      (node (ref "L3") (pin "2") (pinfunction "2_2") (pintype "passive"))
      (node (ref "L4") (pin "1") (pinfunction "1_1") (pintype "passive"))
    )
    (net (code "22") (name "Net-(C18-Pad2)") (class "Default")
      (node (ref "C18") (pin "2") (pinfunction "2_2") (pintype "passive"))
      (node (ref "L6") (pin "1") (pinfunction "1_1") (pintype "passive"))
      (node (ref "L8") (pin "2") (pinfunction "2_2") (pintype "passive"))
    )
    (net (code "23") (name "Net-(C36-Pad2)") (class "Default")
      (node (ref "C36") (pin "2") (pinfunction "2_2") (pintype "passive"))
      (node (ref "L5") (pin "1") (pinfunction "1_1") (pintype "passive"))
      (node (ref "R15") (pin "1") (pinfunction "1_1") (pintype "passive"))
    )
    (net (code "24") (name "Net-(D1-PadC)") (class "Default")
      (node (ref "D1") (pin "C") (pinfunction "C_C") (pintype "passive"))
      (node (ref "R17") (pin "2") (pinfunction "2_2") (pintype "passive"))
    )
    (net (code "25") (name "Net-(D2-PadC)") (class "Default")
      (node (ref "D2") (pin "C") (pinfunction "C_C") (pintype "passive"))
      (node (ref "R21") (pin "1") (pinfunction "1_1") (pintype "passive"))
    )
    (net (code "26") (name "Net-(J$1-SIGNAL)") (class "Default")
      (node (ref "J$1") (pin "SIG") (pinfunction "SIGNAL_SIG") (pintype "bidirectional"))
      (node (ref "L4") (pin "2") (pinfunction "2_2") (pintype "passive"))
    )
    (net (code "27") (name "Net-(TX/RX-AVDD_PFD_CHP)") (class "Default")
      (node (ref "C23") (pin "2") (pinfunction "2_2") (pintype "passive"))
      (node (ref "TX/RX") (pin "25") (pinfunction "AVDD_PFD_CHP_25") (pintype "bidirectional"))
    )
    (net (code "28") (name "Net-(TX/RX-DCPL)") (class "Default")
      (node (ref "C32") (pin "2") (pinfunction "2_2") (pintype "passive"))
      (node (ref "TX/RX") (pin "6") (pinfunction "DCPL_6") (pintype "bidirectional"))
    )
    (net (code "29") (name "Net-(TX/RX-DCPL_PFD_CHP)") (class "Default")
      (node (ref "C24") (pin "2") (pinfunction "2_2") (pintype "passive"))
      (node (ref "TX/RX") (pin "26") (pinfunction "DCPL_PFD_CHP_26") (pintype "bidirectional"))
    )
    (net (code "30") (name "Net-(TX/RX-DCPL_VCO)") (class "Default")
      (node (ref "C20") (pin "1") (pinfunction "1_1") (pintype "passive"))
      (node (ref "TX/RX") (pin "21") (pinfunction "DCPL_VCO_21") (pintype "bidirectional"))
    )
    (net (code "31") (name "Net-(TX/RX-DCPL_XOSC)") (class "Default")
      (node (ref "C27") (pin "2") (pinfunction "2_2") (pintype "passive"))
      (node (ref "TX/RX") (pin "29") (pinfunction "DCPL_XOSC_29") (pintype "bidirectional"))
    )
    (net (code "32") (name "Net-(TX/RX-EXT_XOSC)") (class "Default")
      (node (ref "R14") (pin "1") (pinfunction "1_1") (pintype "passive"))
      (node (ref "TX/RX") (pin "32") (pinfunction "EXT_XOSC_32") (pintype "bidirectional"))
    )
    (net (code "33") (name "Net-(TX/RX-LNA_N)") (class "Default")
      (node (ref "C19") (pin "1") (pinfunction "1_1") (pintype "passive"))
      (node (ref "L7") (pin "1") (pinfunction "1_1") (pintype "passive"))
      (node (ref "L8") (pin "1") (pinfunction "1_1") (pintype "passive"))
      (node (ref "TX/RX") (pin "20") (pinfunction "LNA_N_20") (pintype "bidirectional"))
    )
    (net (code "34") (name "Net-(TX/RX-LNA_P)") (class "Default")
      (node (ref "C18") (pin "1") (pinfunction "1_1") (pintype "passive"))
      (node (ref "L7") (pin "2") (pinfunction "2_2") (pintype "passive"))
      (node (ref "L9") (pin "1") (pinfunction "1_1") (pintype "passive"))
      (node (ref "TX/RX") (pin "19") (pinfunction "LNA_P_19") (pintype "bidirectional"))
    )
    (net (code "35") (name "Net-(TX/RX-LPF0)") (class "Default")
      (node (ref "C22") (pin "2") (pinfunction "2_2") (pintype "passive"))
      (node (ref "TX/RX") (pin "23") (pinfunction "LPF0_23") (pintype "bidirectional"))
    )
    (net (code "36") (name "Net-(TX/RX-LPF1)") (class "Default")
      (node (ref "C22") (pin "1") (pinfunction "1_1") (pintype "passive"))
      (node (ref "TX/RX") (pin "24") (pinfunction "LPF1_24") (pintype "bidirectional"))
    )
    (net (code "37") (name "Net-(TX/RX-PA)") (class "Default")
      (node (ref "C13") (pin "1") (pinfunction "1_1") (pintype "passive"))
      (node (ref "L5") (pin "2") (pinfunction "2_2") (pintype "passive"))
      (node (ref "TX/RX") (pin "17") (pinfunction "PA_17") (pintype "bidirectional"))
    )
    (net (code "38") (name "Net-(TX/RX-RBIAS)") (class "Default")
      (node (ref "R16") (pin "1") (pinfunction "1_1") (pintype "passive"))
      (node (ref "TX/RX") (pin "14") (pinfunction "RBIAS_14") (pintype "bidirectional"))
    )
    (net (code "39") (name "Net-(TX/RX-TRX_SW)") (class "Default")
      (node (ref "C15") (pin "2") (pinfunction "2_2") (pintype "passive"))
      (node (ref "L6") (pin "2") (pinfunction "2_2") (pintype "passive"))
      (node (ref "TX/RX") (pin "18") (pinfunction "TRX_SW_18") (pintype "bidirectional"))
    )
    (net (code "40") (name "Net-(TX/RX-XOSC_Q1)") (class "Default")
      (node (ref "C29") (pin "2") (pinfunction "2_2") (pintype "passive"))
      (node (ref "TX/RX") (pin "30") (pinfunction "XOSC_Q1_30") (pintype "bidirectional"))
      (node (ref "Y3") (pin "3") (pinfunction "2_3") (pintype "passive"))
    )
    (net (code "41") (name "Net-(TX/RX-XOSC_Q2)") (class "Default")
      (node (ref "C28") (pin "2") (pinfunction "2_2") (pintype "passive"))
      (node (ref "TX/RX") (pin "31") (pinfunction "XOSC_Q2_31") (pintype "bidirectional"))
      (node (ref "Y3") (pin "1") (pinfunction "1_1") (pintype "passive"))
    )
    (net (code "42") (name "Net-(U$1-PadIN)") (class "Default")
      (node (ref "U$1") (pin "IN") (pinfunction "IN_IN") (pintype "bidirectional"))
      (node (ref "U$2") (pin "OUT") (pinfunction "OUT_OUT") (pintype "bidirectional"))
    )
    (net (code "43") (name "Net-(U$4-G)") (class "Default")
      (node (ref "R6") (pin "2") (pinfunction "2_2") (pintype "passive"))
      (node (ref "U$4") (pin "4") (pinfunction "G_4") (pintype "bidirectional"))
    )
    (net (code "44") (name "Net-(U$6-G)") (class "Default")
      (node (ref "R7") (pin "1") (pinfunction "1_1") (pintype "passive"))
      (node (ref "U$6") (pin "4") (pinfunction "G_4") (pintype "bidirectional"))
    )
    (net (code "45") (name "Net-(U1-PA00(XIN32{slash}SER1:0{slash}TC2:0))") (class "Default")
      (node (ref "C6") (pin "1") (pinfunction "1_1") (pintype "passive"))
      (node (ref "U1") (pin "1") (pinfunction "PA00(XIN32/SER1:0/TC2:0)_1") (pintype "bidirectional"))
      (node (ref "Y1") (pin "P$2") (pinfunction "2_P$2") (pintype "passive"))
    )
    (net (code "46") (name "Net-(U1-PA01(XOUT32{slash}SER1:1{slash}TC2:1))") (class "Default")
      (node (ref "C7") (pin "1") (pinfunction "1_1") (pintype "passive"))
      (node (ref "U1") (pin "2") (pinfunction "PA01(XOUT32/SER1:1/TC2:1)_2") (pintype "bidirectional"))
      (node (ref "Y1") (pin "P$1") (pinfunction "1_P$1") (pintype "passive"))
    )
    (net (code "47") (name "Net-(U1-VDDANA)") (class "Default")
      (node (ref "C3") (pin "1") (pinfunction "1_1") (pintype "passive"))
      (node (ref "L1") (pin "2") (pinfunction "2_2") (pintype "passive"))
      (node (ref "U1") (pin "6") (pinfunction "VDDANA_6") (pintype "bidirectional"))
    )
    (net (code "48") (name "Net-(U1-VDDCORE)") (class "Default")
      (node (ref "C4") (pin "1") (pinfunction "1_1") (pintype "passive"))
      (node (ref "U1") (pin "43") (pinfunction "VDDCORE_43") (pintype "bidirectional"))
    )
    (net (code "49") (name "Net-(U4-3D-FIX)") (class "Default")
      (node (ref "D1") (pin "A") (pinfunction "A_A") (pintype "passive"))
      (node (ref "U4") (pin "P$5") (pinfunction "3D-FIX_P$5") (pintype "bidirectional"))
    )
    (net (code "50") (name "PROG") (class "Default")
      (node (ref "R13") (pin "2") (pinfunction "2_2") (pintype "passive"))
      (node (ref "S2") (pin "1") (pinfunction "1_1") (pintype "passive"))
      (node (ref "S2") (pin "2") (pinfunction "1_2") (pintype "passive"))
      (node (ref "U1") (pin "10") (pinfunction "PA05(AIN5/SER0:1/TC0:1)_10") (pintype "bidirectional"))
    )
    (net (code "51") (name "RAW") (class "Default")
      (node (ref "JP5") (pin "VCC") (pinfunction "2_VCC") (pintype "passive"))
      (node (ref "R18") (pin "2") (pinfunction "2_2") (pintype "passive"))
      (node (ref "U$1") (pin "VCC") (pinfunction "VCC_VCC") (pintype "bidirectional"))
      (node (ref "U$2") (pin "VCC") (pinfunction "VCC_VCC") (pintype "bidirectional"))
      (node (ref "U$3") (pin "S1") (pinfunction "S_S1") (pintype "bidirectional"))
      (node (ref "U$3") (pin "S2") (pinfunction "S_S2") (pintype "bidirectional"))
      (node (ref "U$3") (pin "S3") (pinfunction "S_S3") (pintype "bidirectional"))
    )
    (net (code "52") (name "SENSE_A") (class "Default")
      (node (ref "R10") (pin "2") (pinfunction "2_2") (pintype "passive"))
      (node (ref "R9") (pin "1") (pinfunction "1_1") (pintype "passive"))
      (node (ref "U1") (pin "7") (pinfunction "PB08(AIN2/SER4:0/TC4:0)_7") (pintype "bidirectional"))
    )
    (net (code "53") (name "SENSE_B") (class "Default")
      (node (ref "R11") (pin "2") (pinfunction "2_2") (pintype "passive"))
      (node (ref "R12") (pin "1") (pinfunction "1_1") (pintype "passive"))
      (node (ref "U1") (pin "8") (pinfunction "PB09(AIN3/SER4:1/TC4:1)_8") (pintype "bidirectional"))
    )
    (net (code "54") (name "SENSE_BAT") (class "Default")
      (node (ref "R18") (pin "1") (pinfunction "1_1") (pintype "passive"))
      (node (ref "R19") (pin "2") (pinfunction "2_2") (pintype "passive"))
      (node (ref "U1") (pin "11") (pinfunction "PA06(AIN6/SER0:2/TC1:0)_11") (pintype "bidirectional"))
    )
    (net (code "55") (name "SPI1_MISO") (class "Default")
      (node (ref "MEM") (pin "SO") (pinfunction "SO_SO") (pintype "bidirectional"))
      (node (ref "TX/RX") (pin "9") (pinfunction "GPOI1_9") (pintype "bidirectional"))
      (node (ref "U1") (pin "25") (pinfunction "PA16(I2C/SER1:0+)_25") (pintype "bidirectional"))
    )
    (net (code "56") (name "SPI1_MOSI") (class "Default")
      (node (ref "MEM") (pin "SI") (pinfunction "SI_SI") (pintype "bidirectional"))
      (node (ref "TX/RX") (pin "7") (pinfunction "SI_7") (pintype "bidirectional"))
      (node (ref "U1") (pin "28") (pinfunction "PA19(SER1:3+)_28") (pintype "bidirectional"))
    )
    (net (code "57") (name "SPI1_SCK") (class "Default")
      (node (ref "MEM") (pin "SCK") (pinfunction "SCK_SCK") (pintype "bidirectional"))
      (node (ref "TX/RX") (pin "8") (pinfunction "SCLK_8") (pintype "bidirectional"))
      (node (ref "U1") (pin "26") (pinfunction "PA17(I2C/SER1:1+)_26") (pintype "bidirectional"))
    )
    (net (code "58") (name "SPI2_MISO") (class "Default")
      (node (ref "U$5") (pin "6") (pinfunction "SDO_6") (pintype "bidirectional"))
      (node (ref "U1") (pin "22") (pinfunction "PA13(I2C/SER2:1+)_22") (pintype "bidirectional"))
      (node (ref "U3") (pin "12") (pinfunction "SDO_12") (pintype "bidirectional"))
    )
    (net (code "59") (name "SPI2_MOSI") (class "Default")
      (node (ref "U$5") (pin "7") (pinfunction "SDI/SDA_7") (pintype "bidirectional"))
      (node (ref "U1") (pin "23") (pinfunction "PA14(XIN/SER2:2+)_23") (pintype "bidirectional"))
      (node (ref "U3") (pin "13") (pinfunction "SDA_13") (pintype "bidirectional"))
    )
    (net (code "60") (name "SPI2_SCK") (class "Default")
      (node (ref "U$5") (pin "8") (pinfunction "SCLK_8") (pintype "bidirectional"))
      (node (ref "U1") (pin "24") (pinfunction "PA15(XOUT/SER2:3+)_24") (pintype "bidirectional"))
      (node (ref "U3") (pin "14") (pinfunction "SCL_14") (pintype "bidirectional"))
    )
    (net (code "61") (name "SWCLK") (class "Default")
      (node (ref "JP1") (pin "4") (pinfunction "SWDCLK/TCK_4") (pintype "bidirectional"))
      (node (ref "U1") (pin "45") (pinfunction "PA30(SWCLK/SER1:2+)_45") (pintype "bidirectional"))
    )
    (net (code "62") (name "SWDIO") (class "Default")
      (node (ref "JP1") (pin "2") (pinfunction "SWDIO/TMS_2") (pintype "bidirectional"))
      (node (ref "U1") (pin "46") (pinfunction "PA31(SWDIO/SER1:3+)_46") (pintype "bidirectional"))
    )
    (net (code "63") (name "USB_D+") (class "Default")
      (node (ref "JP4") (pin "D+") (pinfunction "D+_D+") (pintype "bidirectional"))
      (node (ref "U1") (pin "34") (pinfunction "PA25(SER3:3+)_34") (pintype "bidirectional"))
    )
    (net (code "64") (name "USB_D-") (class "Default")
      (node (ref "JP4") (pin "D-") (pinfunction "D-_D-") (pintype "bidirectional"))
      (node (ref "U1") (pin "33") (pinfunction "PA24(SER3:2+)_33") (pintype "bidirectional"))
    )
    (net (code "65") (name "unconnected-(1U2-BP-Pad4)") (class "Default")
      (node (ref "1U2") (pin "4") (pinfunction "BP_4") (pintype "input"))
    )
    (net (code "66") (name "unconnected-(JP1-GNDDTCT-Pad9)") (class "Default")
      (node (ref "JP1") (pin "9") (pinfunction "GNDDTCT_9") (pintype "bidirectional"))
    )
    (net (code "67") (name "unconnected-(JP1-KEY-Pad7)") (class "Default")
      (node (ref "JP1") (pin "7") (pinfunction "KEY_7") (pintype "bidirectional"))
    )
    (net (code "68") (name "unconnected-(JP1-NC{slash}TDI-Pad8)") (class "Default")
      (node (ref "JP1") (pin "8") (pinfunction "NC/TDI_8") (pintype "bidirectional"))
    )
    (net (code "69") (name "unconnected-(JP1-SWO{slash}TDO-Pad6)") (class "Default")
      (node (ref "JP1") (pin "6") (pinfunction "SWO/TDO_6") (pintype "bidirectional"))
    )
    (net (code "70") (name "unconnected-(JP4-PadVBUS)") (class "Default")
      (node (ref "JP4") (pin "VBUS") (pinfunction "VBUS_VBUS") (pintype "bidirectional"))
    )
    (net (code "71") (name "unconnected-(TX/RX-GPIO0-Pad10)") (class "Default")
      (node (ref "TX/RX") (pin "10") (pinfunction "GPIO0_10") (pintype "bidirectional"))
    )
    (net (code "72") (name "unconnected-(TX/RX-GPIO2-Pad4)") (class "Default")
      (node (ref "TX/RX") (pin "4") (pinfunction "GPIO2_4") (pintype "bidirectional"))
    )
    (net (code "73") (name "unconnected-(TX/RX-GPIO3-Pad3)") (class "Default")
      (node (ref "TX/RX") (pin "3") (pinfunction "GPIO3_3") (pintype "bidirectional"))
    )
    (net (code "74") (name "unconnected-(TX/RX-N.C.-Pad16)") (class "Default")
      (node (ref "TX/RX") (pin "16") (pinfunction "N.C._16") (pintype "bidirectional"))
    )
    (net (code "75") (name "unconnected-(TX/RX-RESET_N-Pad2)") (class "Default")
      (node (ref "TX/RX") (pin "2") (pinfunction "RESET_N_2") (pintype "bidirectional"))
    )
    (net (code "76") (name "unconnected-(U$1-PadCLR)") (class "Default")
      (node (ref "U$1") (pin "CLR") (pinfunction "CLR_CLR") (pintype "bidirectional"))
    )
    (net (code "77") (name "unconnected-(U$1-~{OUT}-Pad!OUT)") (class "Default")
      (node (ref "U$1") (pin "!OUT") (pinfunction "~{OUT}_!OUT") (pintype "bidirectional"))
    )
    (net (code "78") (name "unconnected-(U$7-ST-PadP$4)") (class "Default")
      (node (ref "U$7") (pin "P$4") (pinfunction "ST_P$4") (pintype "bidirectional"))
    )
    (net (code "79") (name "unconnected-(U1-PA02(AIN0{slash}DAC)-Pad3)") (class "Default")
      (node (ref "U1") (pin "3") (pinfunction "PA02(AIN0/DAC)_3") (pintype "bidirectional"))
    )
    (net (code "80") (name "unconnected-(U1-PA03(AIN1{slash}REFA)-Pad4)") (class "Default")
      (node (ref "U1") (pin "4") (pinfunction "PA03(AIN1/REFA)_4") (pintype "bidirectional"))
    )
    (net (code "81") (name "unconnected-(U1-PA04(AIN4{slash}REFB{slash}SER0:0{slash}TC0:0)-Pad9)") (class "Default")
      (node (ref "U1") (pin "9") (pinfunction "PA04(AIN4/REFB/SER0:0/TC0:0)_9") (pintype "bidirectional"))
    )
    (net (code "82") (name "unconnected-(U1-PA08(I2C{slash}AIN16{slash}SER0:0+)-Pad13)") (class "Default")
      (node (ref "U1") (pin "13") (pinfunction "PA08(I2C/AIN16/SER0:0+)_13") (pintype "bidirectional"))
    )
    (net (code "83") (name "unconnected-(U1-PA09(I2C{slash}AIN17{slash}SER0:1+)-Pad14)") (class "Default")
      (node (ref "U1") (pin "14") (pinfunction "PA09(I2C/AIN17/SER0:1+)_14") (pintype "bidirectional"))
    )
    (net (code "84") (name "unconnected-(U1-PA10(AIN18{slash}SER0:2+)-Pad15)") (class "Default")
      (node (ref "U1") (pin "15") (pinfunction "PA10(AIN18/SER0:2+)_15") (pintype "bidirectional"))
    )
    (net (code "85") (name "unconnected-(U1-PA11(AIN19{slash}SER0:3+)-Pad16)") (class "Default")
      (node (ref "U1") (pin "16") (pinfunction "PA11(AIN19/SER0:3+)_16") (pintype "bidirectional"))
    )
    (net (code "86") (name "unconnected-(U1-PA22(I2C{slash}SER3:0+)-Pad31)") (class "Default")
      (node (ref "U1") (pin "31") (pinfunction "PA22(I2C/SER3:0+)_31") (pintype "bidirectional"))
    )
    (net (code "87") (name "unconnected-(U1-PA23(I2C{slash}SER3:0+)-Pad32)") (class "Default")
      (node (ref "U1") (pin "32") (pinfunction "PA23(I2C/SER3:0+)_32") (pintype "bidirectional"))
    )
    (net (code "88") (name "unconnected-(U1-PA28-Pad41)") (class "Default")
      (node (ref "U1") (pin "41") (pinfunction "PA28_41") (pintype "bidirectional"))
    )
    (net (code "89") (name "unconnected-(U1-PB10(SER4:2+)-Pad19)") (class "Default")
      (node (ref "U1") (pin "19") (pinfunction "PB10(SER4:2+)_19") (pintype "bidirectional"))
    )
    (net (code "90") (name "unconnected-(U1-PB11(SER4:3+)-Pad20)") (class "Default")
      (node (ref "U1") (pin "20") (pinfunction "PB11(SER4:3+)_20") (pintype "bidirectional"))
    )
    (net (code "91") (name "unconnected-(U3-INT1-Pad8)") (class "Default")
      (node (ref "U3") (pin "8") (pinfunction "INT1_8") (pintype "bidirectional"))
    )
    (net (code "92") (name "unconnected-(U3-INT2-Pad9)") (class "Default")
      (node (ref "U3") (pin "9") (pinfunction "INT2_9") (pintype "bidirectional"))
    )
    (net (code "93") (name "unconnected-(U3-NC-Pad3)") (class "Default")
      (node (ref "U3") (pin "3") (pinfunction "NC_3") (pintype "bidirectional"))
    )
    (net (code "94") (name "unconnected-(U3-NC-Pad10)") (class "Default")
      (node (ref "U3") (pin "10") (pinfunction "NC_10") (pintype "bidirectional"))
    )
    (net (code "95") (name "unconnected-(U3-NC-Pad11)") (class "Default")
      (node (ref "U3") (pin "11") (pinfunction "NC_11") (pintype "bidirectional"))
    )
    (net (code "96") (name "unconnected-(U4-1PPS-PadP$13)") (class "Default")
      (node (ref "U4") (pin "P$13") (pinfunction "1PPS_P$13") (pintype "bidirectional"))
    )
    (net (code "97") (name "unconnected-(U4-EX_ANT-PadP$11)") (class "Default")
      (node (ref "U4") (pin "P$11") (pinfunction "EX_ANT_P$11") (pintype "bidirectional"))
    )
    (net (code "98") (name "unconnected-(U4-NC-PadP$6)") (class "Default")
      (node (ref "U4") (pin "P$6") (pinfunction "NC_P$6") (pintype "bidirectional"))
    )
    (net (code "99") (name "unconnected-(U4-NC-PadP$7)") (class "Default")
      (node (ref "U4") (pin "P$7") (pinfunction "NC_P$7") (pintype "bidirectional"))
    )
    (net (code "100") (name "unconnected-(U4-NC-PadP$15)") (class "Default")
      (node (ref "U4") (pin "P$15") (pinfunction "NC_P$15") (pintype "bidirectional"))
    )
    (net (code "101") (name "unconnected-(U4-NC-PadP$16)") (class "Default")
      (node (ref "U4") (pin "P$16") (pinfunction "NC_P$16") (pintype "bidirectional"))
    )
    (net (code "102") (name "unconnected-(U4-NC-PadP$17)") (class "Default")
      (node (ref "U4") (pin "P$17") (pinfunction "NC_P$17") (pintype "bidirectional"))
    )
    (net (code "103") (name "unconnected-(U4-NC-PadP$18)") (class "Default")
      (node (ref "U4") (pin "P$18") (pinfunction "NC_P$18") (pintype "bidirectional"))
    )
    (net (code "104") (name "unconnected-(U4-NC-PadP$20)") (class "Default")
      (node (ref "U4") (pin "P$20") (pinfunction "NC_P$20") (pintype "bidirectional"))
    )
    (net (code "105") (name "unconnected-(U4-NRESET-PadP$2)") (class "Default")
      (node (ref "U4") (pin "P$2") (pinfunction "NRESET_P$2") (pintype "bidirectional"))
    )
    (net (code "106") (name "unconnected-(U4-RTCM-PadP$14)") (class "Default")
      (node (ref "U4") (pin "P$14") (pinfunction "RTCM_P$14") (pintype "bidirectional"))
    )
    (net (code "107") (name "unconnected-(U4-VBACKUP-PadP$4)") (class "Default")
      (node (ref "U4") (pin "P$4") (pinfunction "VBACKUP_P$4") (pintype "bidirectional"))
    )
  )
)
